# IntegratedConnectors.net
KiCad netlist of a schematic drawn in Altium Designer
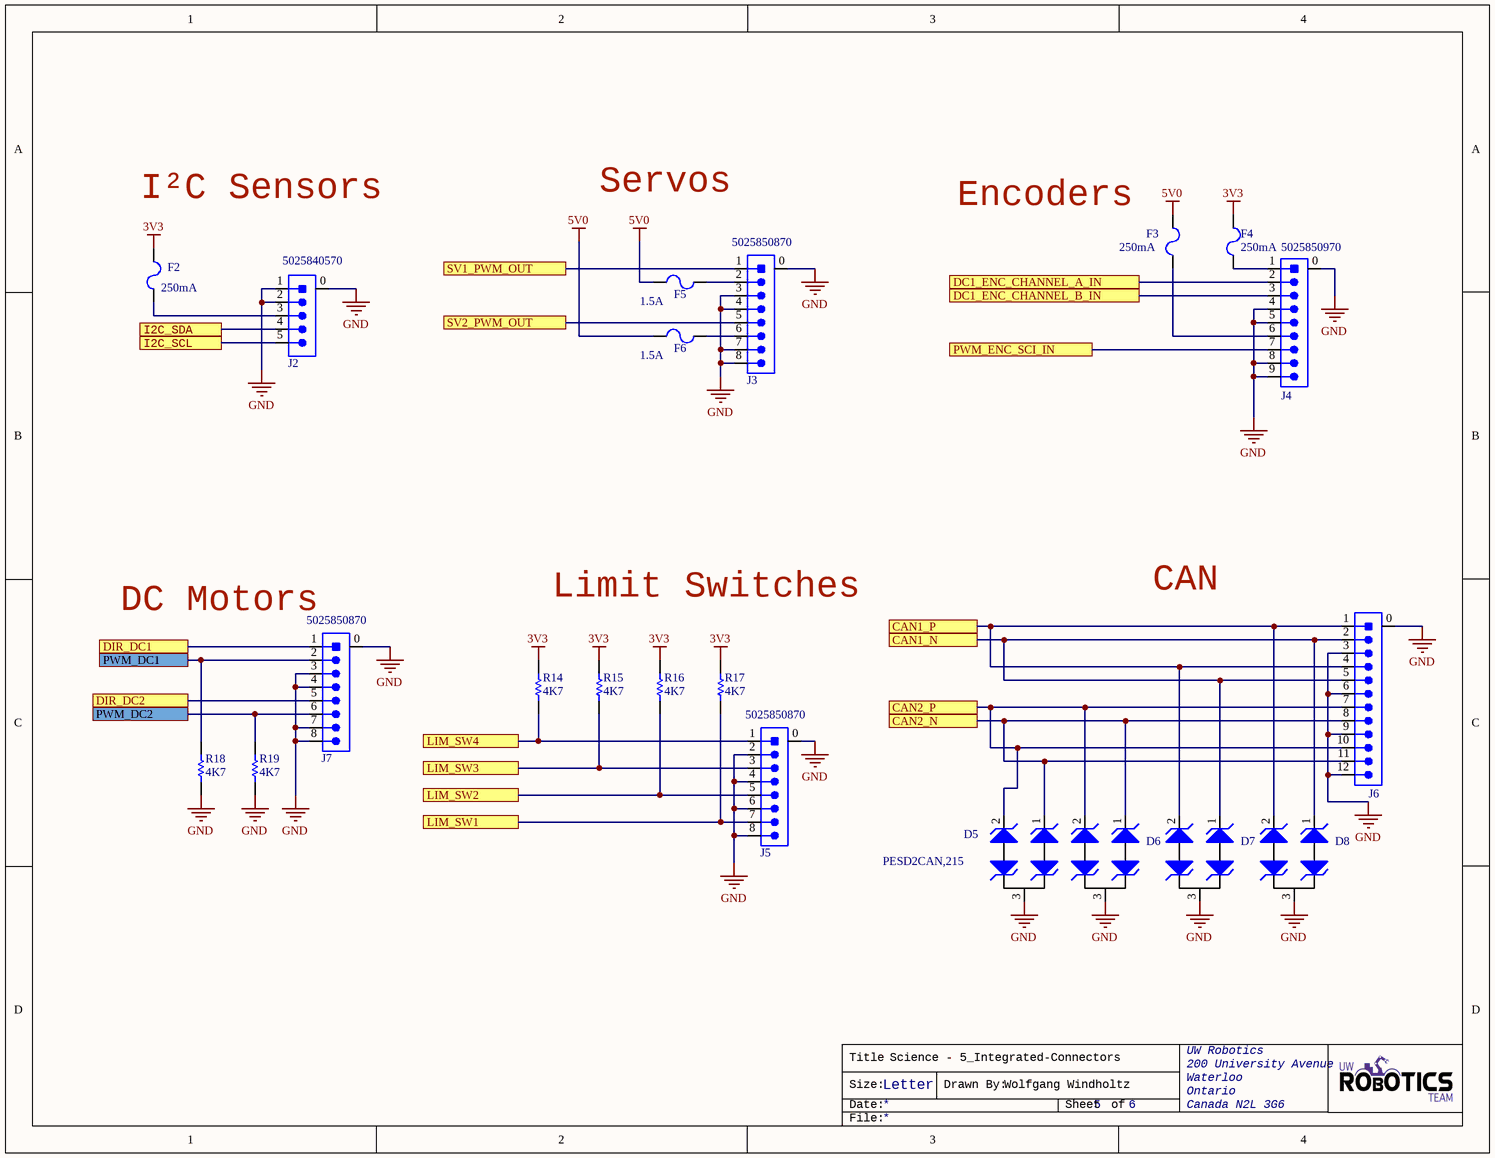
[diagram p0: IntegratedConnectors.SchDoc]

(export (version "E")
  (design (tool "Eeschema 10.0.6"))
  (components
    (comp (ref "D5")
      (value "TVS_DIODE_CAN")
      (footprint "TVS_DIODE_CAN")
      (description "TVS DIODE 24V 41V SOT323-3")
      (fields
        (field (name "MANUFACTURER") "Nexperia USA Inc.")
        (field (name "MANUFACTURER PART NUMBER") "PESD2CAN,215")
      )
      (libsource (lib "UWRT_Schematic_Library_2020") (part "TVS_DIODE_CAN"))
    )
    (comp (ref "D6")
      (value "TVS_DIODE_CAN")
      (footprint "TVS_DIODE_CAN")
      (description "TVS DIODE 24V 41V SOT323-3")
      (fields (field (name "MANUFACTURER") "Nexperia USA Inc."))
      (libsource (lib "UWRT_Schematic_Library_2020") (part "TVS_DIODE_CAN"))
    )
    (comp (ref "D7")
      (value "TVS_DIODE_CAN")
      (footprint "TVS_DIODE_CAN")
      (description "TVS DIODE 24V 41V SOT323-3")
      (fields (field (name "MANUFACTURER") "Nexperia USA Inc."))
      (libsource (lib "UWRT_Schematic_Library_2020") (part "TVS_DIODE_CAN"))
    )
    (comp (ref "D8")
      (value "TVS_DIODE_CAN")
      (footprint "TVS_DIODE_CAN")
      (description "TVS DIODE 24V 41V SOT323-3")
      (fields (field (name "MANUFACTURER") "Nexperia USA Inc."))
      (libsource (lib "UWRT_Schematic_Library_2020") (part "TVS_DIODE_CAN"))
    )
    (comp (ref "F2")
      (value "FUSE_250mA_0603")
      (footprint "FUSE_0603")
      (description "FUSE SMD 250mA 32V")
      (fields (field (name "CURRENT RATING") "250mA"))
      (libsource (lib "UWRT_Schematic_Library_2020") (part "FUSE_250mA_0603"))
    )
    (comp (ref "F3")
      (value "FUSE_250mA_0603")
      (footprint "FUSE_0603")
      (description "FUSE SMD 250mA 32V")
      (fields (field (name "CURRENT RATING") "250mA"))
      (libsource (lib "UWRT_Schematic_Library_2020") (part "FUSE_250mA_0603"))
    )
    (comp (ref "F4")
      (value "FUSE_250mA_0603")
      (footprint "FUSE_0603")
      (description "FUSE SMD 250mA 32V")
      (fields (field (name "CURRENT RATING") "250mA"))
      (libsource (lib "UWRT_Schematic_Library_2020") (part "FUSE_250mA_0603"))
    )
    (comp (ref "F5")
      (value "FUSE_1.5A_0603")
      (footprint "FUSE_0603")
      (description "FUSE SMD 1.5A 32V")
      (fields (field (name "CURRENT RATING") "1.5A"))
      (libsource (lib "UWRT_Schematic_Library_2020") (part "FUSE_1.5A_0603"))
    )
    (comp (ref "F6")
      (value "FUSE_1.5A_0603")
      (footprint "FUSE_0603")
      (description "FUSE SMD 1.5A 32V")
      (fields (field (name "CURRENT RATING") "1.5A"))
      (libsource (lib "UWRT_Schematic_Library_2020") (part "FUSE_1.5A_0603"))
    )
    (comp (ref "J2")
      (value "CON_5M_SM_VERT")
      (footprint "MOLEX-5025840570")
      (description "CONN HEADER SMD VERTICAL 1.5MM PITCH")
      (fields (field (name "MANUFACTURER PART NUMBER 1") "5025840570"))
      (libsource (lib "UWRT_Schematic_Library_2020") (part "CON_5M_SM_VERT"))
    )
    (comp (ref "J3")
      (value "CON_8M_SM_RA")
      (footprint "MOLEX-5025850870")
      (description "CONN HEADER SMD RIGHT ANGLE 1.5 MM PITCH")
      (fields (field (name "MANUFACTURER") "Molex") (field (name "MANUFACTURER PART NUMBER") "5025850870"))
      (libsource (lib "UWRT_Schematic_Library_2020") (part "CON_8M_SM_RA"))
    )
    (comp (ref "J4")
      (value "CON_9M_SM_RA")
      (footprint "Molex-5025850970")
      (description "Board Connector, 9 Contact(s), 1 Row(s), Female, Right Angle, Surface Mount Terminal, Receptacle")
      (fields (field (name "MANUFACTURER") "Molex") (field (name "MANUFACTURER PART NUMBER") "5025850970"))
      (libsource (lib "UWRT_Schematic_Library_2020") (part "CON_9M_SM_RA"))
    )
    (comp (ref "J5")
      (value "CON_8M_SM_RA")
      (footprint "MOLEX-5025850870")
      (description "CONN HEADER SMD RIGHT ANGLE 1.5 MM PITCH")
      (fields (field (name "MANUFACTURER") "Molex") (field (name "MANUFACTURER PART NUMBER") "5025850870"))
      (libsource (lib "UWRT_Schematic_Library_2020") (part "CON_8M_SM_RA"))
    )
    (comp (ref "J6")
      (value "~")
      (footprint "MOLEX-5025851270")
      (description "CONN HEADER SMD RIGHT ANGLE 1.5MM PITCH")
      (libsource (lib "UWRT_Schematic_Library_2020") (part "CON_12M_SM_RA"))
    )
    (comp (ref "J7")
      (value "CON_8M_SM_RA")
      (footprint "MOLEX-5025850870")
      (description "CONN HEADER SMD RIGHT ANGLE 1.5 MM PITCH")
      (fields (field (name "MANUFACTURER") "Molex") (field (name "MANUFACTURER PART NUMBER") "5025850870"))
      (libsource (lib "UWRT_Schematic_Library_2020") (part "CON_8M_SM_RA"))
    )
    (comp (ref "R14")
      (value "4K7")
      (footprint "RESC0603(1608)_N")
      (description "RES SMD 4.7K OHM 5% 1/10W 0603")
      (fields (field (name "MANUFACTURER") "Yageo") (field (name "MPN") "RC0603JR-074K7L"))
      (libsource (lib "UWRT_Schematic_Library_2020") (part "RES_4K7_0603"))
    )
    (comp (ref "R15")
      (value "4K7")
      (footprint "RESC0603(1608)_N")
      (description "RES SMD 4.7K OHM 5% 1/10W 0603")
      (fields (field (name "MANUFACTURER") "Yageo") (field (name "MPN") "RC0603JR-074K7L"))
      (libsource (lib "UWRT_Schematic_Library_2020") (part "RES_4K7_0603"))
    )
    (comp (ref "R16")
      (value "4K7")
      (footprint "RESC0603(1608)_N")
      (description "RES SMD 4.7K OHM 5% 1/10W 0603")
      (fields (field (name "MANUFACTURER") "Yageo") (field (name "MPN") "RC0603JR-074K7L"))
      (libsource (lib "UWRT_Schematic_Library_2020") (part "RES_4K7_0603"))
    )
    (comp (ref "R17")
      (value "4K7")
      (footprint "RESC0603(1608)_N")
      (description "RES SMD 4.7K OHM 5% 1/10W 0603")
      (fields (field (name "MANUFACTURER") "Yageo") (field (name "MPN") "RC0603JR-074K7L"))
      (libsource (lib "UWRT_Schematic_Library_2020") (part "RES_4K7_0603"))
    )
    (comp (ref "R18")
      (value "4K7")
      (footprint "RESC0603(1608)_N")
      (description "RES SMD 4.7K OHM 5% 1/10W 0603")
      (fields (field (name "MANUFACTURER") "Yageo") (field (name "MPN") "RC0603JR-074K7L"))
      (libsource (lib "UWRT_Schematic_Library_2020") (part "RES_4K7_0603"))
    )
    (comp (ref "R19")
      (value "4K7")
      (footprint "RESC0603(1608)_N")
      (description "RES SMD 4.7K OHM 5% 1/10W 0603")
      (fields (field (name "MANUFACTURER") "Yageo") (field (name "MPN") "RC0603JR-074K7L"))
      (libsource (lib "UWRT_Schematic_Library_2020") (part "RES_4K7_0603"))
    )
  )
  (nets
    (net (code "1") (name "/CAN1_N") (class "Default")
      (node (ref "D7") (pin "1") (pinfunction "1_1") (pintype "passive"))
      (node (ref "D8") (pin "1") (pinfunction "1_1") (pintype "passive"))
      (node (ref "J6") (pin "2") (pinfunction "2_2") (pintype "passive"))
      (node (ref "J6") (pin "5") (pinfunction "5_5") (pintype "passive"))
    )
    (net (code "2") (name "/CAN1_P") (class "Default")
      (node (ref "D7") (pin "2") (pinfunction "2_2") (pintype "passive"))
      (node (ref "D8") (pin "2") (pinfunction "2_2") (pintype "passive"))
      (node (ref "J6") (pin "1") (pinfunction "1_1") (pintype "passive"))
      (node (ref "J6") (pin "4") (pinfunction "4_4") (pintype "passive"))
    )
    (net (code "3") (name "/CAN2_N") (class "Default")
      (node (ref "D5") (pin "1") (pinfunction "1_1") (pintype "passive"))
      (node (ref "D6") (pin "1") (pinfunction "1_1") (pintype "passive"))
      (node (ref "J6") (pin "11") (pinfunction "11_11") (pintype "passive"))
      (node (ref "J6") (pin "8") (pinfunction "6_8") (pintype "passive"))
    )
    (net (code "4") (name "/CAN2_P") (class "Default")
      (node (ref "D5") (pin "2") (pinfunction "2_2") (pintype "passive"))
      (node (ref "D6") (pin "2") (pinfunction "2_2") (pintype "passive"))
      (node (ref "J6") (pin "10") (pinfunction "10_10") (pintype "passive"))
      (node (ref "J6") (pin "7") (pinfunction "6_7") (pintype "passive"))
    )
    (net (code "5") (name "/DC1_ENC_CHANNEL_A_IN") (class "Default")
      (node (ref "J4") (pin "2") (pinfunction "2_2") (pintype "passive"))
    )
    (net (code "6") (name "/DC1_ENC_CHANNEL_B_IN") (class "Default")
      (node (ref "J4") (pin "3") (pinfunction "3_3") (pintype "passive"))
    )
    (net (code "7") (name "/DIR_DC1") (class "Default")
      (node (ref "J7") (pin "1") (pinfunction "1_1") (pintype "passive"))
    )
    (net (code "8") (name "/DIR_DC2") (class "Default")
      (node (ref "J7") (pin "5") (pinfunction "5_5") (pintype "passive"))
    )
    (net (code "9") (name "/I2C_SCL") (class "Default")
      (node (ref "J2") (pin "5") (pinfunction "5_5") (pintype "passive"))
    )
    (net (code "10") (name "/I2C_SDA") (class "Default")
      (node (ref "J2") (pin "4") (pinfunction "4_4") (pintype "passive"))
    )
    (net (code "11") (name "/LIM_SW1") (class "Default")
      (node (ref "J5") (pin "7") (pinfunction "6_7") (pintype "passive"))
      (node (ref "R17") (pin "1") (pinfunction "1_1") (pintype "passive"))
    )
    (net (code "12") (name "/LIM_SW2") (class "Default")
      (node (ref "J5") (pin "5") (pinfunction "5_5") (pintype "passive"))
      (node (ref "R16") (pin "1") (pinfunction "1_1") (pintype "passive"))
    )
    (net (code "13") (name "/LIM_SW3") (class "Default")
      (node (ref "J5") (pin "3") (pinfunction "3_3") (pintype "passive"))
      (node (ref "R15") (pin "1") (pinfunction "1_1") (pintype "passive"))
    )
    (net (code "14") (name "/LIM_SW4") (class "Default")
      (node (ref "J5") (pin "1") (pinfunction "1_1") (pintype "passive"))
      (node (ref "R14") (pin "1") (pinfunction "1_1") (pintype "passive"))
    )
    (net (code "15") (name "/PWM_DC1") (class "Default")
      (node (ref "J7") (pin "2") (pinfunction "2_2") (pintype "passive"))
      (node (ref "R18") (pin "1") (pinfunction "1_1") (pintype "passive"))
    )
    (net (code "16") (name "/PWM_DC2") (class "Default")
      (node (ref "J7") (pin "6") (pinfunction "6_6") (pintype "passive"))
      (node (ref "R19") (pin "1") (pinfunction "1_1") (pintype "passive"))
    )
    (net (code "17") (name "/PWM_ENC_SCI_IN") (class "Default")
      (node (ref "J4") (pin "7") (pinfunction "6_7") (pintype "passive"))
    )
    (net (code "18") (name "/SV1_PWM_OUT") (class "Default")
      (node (ref "J3") (pin "1") (pinfunction "1_1") (pintype "passive"))
    )
    (net (code "19") (name "/SV2_PWM_OUT") (class "Default")
      (node (ref "J3") (pin "5") (pinfunction "5_5") (pintype "passive"))
    )
    (net (code "20") (name "3V3") (class "Default")
      (node (ref "F2") (pin "1") (pinfunction "1_1") (pintype "passive"))
      (node (ref "F4") (pin "2") (pinfunction "2_2") (pintype "passive"))
      (node (ref "R14") (pin "2") (pinfunction "2_2") (pintype "passive"))
      (node (ref "R15") (pin "2") (pinfunction "2_2") (pintype "passive"))
      (node (ref "R16") (pin "2") (pinfunction "2_2") (pintype "passive"))
      (node (ref "R17") (pin "2") (pinfunction "2_2") (pintype "passive"))
    )
    (net (code "21") (name "5V0") (class "Default")
      (node (ref "F3") (pin "2") (pinfunction "2_2") (pintype "passive"))
      (node (ref "F5") (pin "2") (pinfunction "2_2") (pintype "passive"))
      (node (ref "F6") (pin "2") (pinfunction "2_2") (pintype "passive"))
    )
    (net (code "22") (name "GND") (class "Default")
      (node (ref "D5") (pin "3") (pinfunction "3_3") (pintype "passive"))
      (node (ref "D6") (pin "3") (pinfunction "3_3") (pintype "passive"))
      (node (ref "D7") (pin "3") (pinfunction "3_3") (pintype "passive"))
      (node (ref "D8") (pin "3") (pinfunction "3_3") (pintype "passive"))
      (node (ref "J2") (pin "0") (pinfunction "0_0") (pintype "passive"))
      (node (ref "J2") (pin "1") (pinfunction "1_1") (pintype "passive"))
      (node (ref "J2") (pin "2") (pinfunction "2_2") (pintype "passive"))
      (node (ref "J3") (pin "0") (pinfunction "0_0") (pintype "passive"))
      (node (ref "J3") (pin "3") (pinfunction "3_3") (pintype "passive"))
      (node (ref "J3") (pin "4") (pinfunction "4_4") (pintype "passive"))
      (node (ref "J3") (pin "7") (pinfunction "6_7") (pintype "passive"))
      (node (ref "J3") (pin "8") (pinfunction "6_8") (pintype "passive"))
      (node (ref "J4") (pin "0") (pinfunction "0_0") (pintype "passive"))
      (node (ref "J4") (pin "4") (pinfunction "4_4") (pintype "passive"))
      (node (ref "J4") (pin "5") (pinfunction "5_5") (pintype "passive"))
      (node (ref "J4") (pin "8") (pinfunction "6_8") (pintype "passive"))
      (node (ref "J4") (pin "9") (pinfunction "9_9") (pintype "passive"))
      (node (ref "J5") (pin "0") (pinfunction "0_0") (pintype "passive"))
      (node (ref "J5") (pin "2") (pinfunction "2_2") (pintype "passive"))
      (node (ref "J5") (pin "4") (pinfunction "4_4") (pintype "passive"))
      (node (ref "J5") (pin "6") (pinfunction "6_6") (pintype "passive"))
      (node (ref "J5") (pin "8") (pinfunction "6_8") (pintype "passive"))
      (node (ref "J6") (pin "0") (pinfunction "0_0") (pintype "passive"))
      (node (ref "J6") (pin "12") (pinfunction "12_12") (pintype "passive"))
      (node (ref "J6") (pin "3") (pinfunction "3_3") (pintype "passive"))
      (node (ref "J6") (pin "6") (pinfunction "6_6") (pintype "passive"))
      (node (ref "J6") (pin "9") (pinfunction "9_9") (pintype "passive"))
      (node (ref "J7") (pin "0") (pinfunction "0_0") (pintype "passive"))
      (node (ref "J7") (pin "3") (pinfunction "3_3") (pintype "passive"))
      (node (ref "J7") (pin "4") (pinfunction "4_4") (pintype "passive"))
      (node (ref "J7") (pin "7") (pinfunction "6_7") (pintype "passive"))
      (node (ref "J7") (pin "8") (pinfunction "6_8") (pintype "passive"))
      (node (ref "R18") (pin "2") (pinfunction "2_2") (pintype "passive"))
      (node (ref "R19") (pin "2") (pinfunction "2_2") (pintype "passive"))
    )
    (net (code "23") (name "Net-(F2-Pad2)") (class "Default")
      (node (ref "F2") (pin "2") (pinfunction "2_2") (pintype "passive"))
      (node (ref "J2") (pin "3") (pinfunction "3_3") (pintype "passive"))
    )
    (net (code "24") (name "Net-(F3-Pad1)") (class "Default")
      (node (ref "F3") (pin "1") (pinfunction "1_1") (pintype "passive"))
      (node (ref "J4") (pin "6") (pinfunction "6_6") (pintype "passive"))
    )
    (net (code "25") (name "Net-(F4-Pad1)") (class "Default")
      (node (ref "F4") (pin "1") (pinfunction "1_1") (pintype "passive"))
      (node (ref "J4") (pin "1") (pinfunction "1_1") (pintype "passive"))
    )
    (net (code "26") (name "Net-(F5-Pad1)") (class "Default")
      (node (ref "F5") (pin "1") (pinfunction "1_1") (pintype "passive"))
      (node (ref "J3") (pin "2") (pinfunction "2_2") (pintype "passive"))
    )
    (net (code "27") (name "Net-(F6-Pad1)") (class "Default")
      (node (ref "F6") (pin "1") (pinfunction "1_1") (pintype "passive"))
      (node (ref "J3") (pin "6") (pinfunction "6_6") (pintype "passive"))
    )
  )
)
